# Processor.net
KiCad netlist of a schematic drawn in Altium Designer
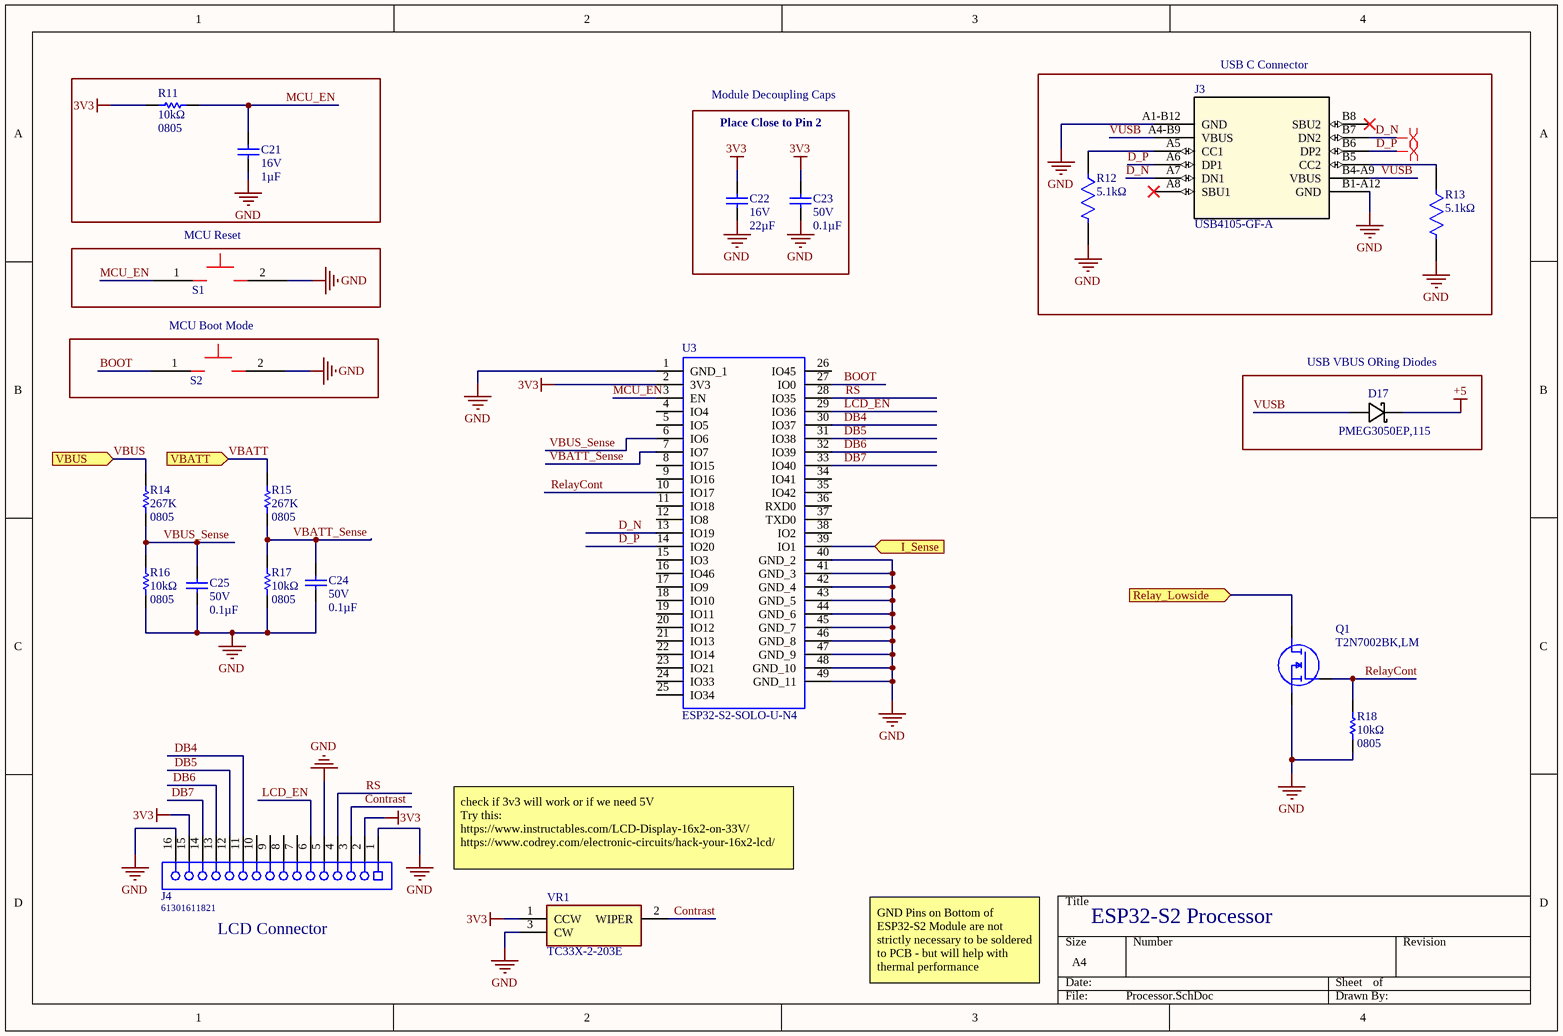
[diagram p0: Processor.SchDoc]

(export (version "E")
  (design (tool "Eeschema 10.0.6"))
  (components
    (comp (ref "C21")
      (value "GRM21BR71C105KA01L")
      (footprint "CAP0805")
      (description "CAP CER 1UF 16V X7R 0805")
      (fields
        (field (name "MANUFACTURER") "Murata Electronics North America")
        (field (name "TOLERANCE") "±10%")
        (field (name "VOLTAGE - RATED") "16V")
        (field (name "CAPACITANCE") "1µF")
      )
      (libsource (lib "Capacitors") (part "GRM21BR71C105KA01L"))
    )
    (comp (ref "C22")
      (value "CL21A226MOCLRNC")
      (footprint "CAP0805")
      (description "CAP CER 22UF 16V X5R 0805")
      (fields
        (field (name "TOLERANCE") "±20%")
        (field (name "VOLTAGE - RATED") "16V")
        (field (name "CAPACITANCE") "22µF")
      )
      (libsource (lib "Capacitors") (part "CL21A226MOCLRNC"))
    )
    (comp (ref "C23")
      (value "C0805C104K5RACTU")
      (footprint "CAP0805")
      (description "CAP CER 0.1UF 50V X7R 0805")
      (fields
        (field (name "TOLERANCE") "±10%")
        (field (name "VOLTAGE - RATED") "50V")
        (field (name "CAPACITANCE") "0.1µF")
      )
      (libsource (lib "Capacitors") (part "C0805C104K5RACTU"))
    )
    (comp (ref "C24")
      (value "C0805C104K5RACTU")
      (footprint "CAP0805")
      (description "CAP CER 0.1UF 50V X7R 0805")
      (fields
        (field (name "TOLERANCE") "±10%")
        (field (name "VOLTAGE - RATED") "50V")
        (field (name "CAPACITANCE") "0.1µF")
      )
      (libsource (lib "Capacitors") (part "C0805C104K5RACTU"))
    )
    (comp (ref "C25")
      (value "C0805C104K5RACTU")
      (footprint "CAP0805")
      (description "CAP CER 0.1UF 50V X7R 0805")
      (fields
        (field (name "TOLERANCE") "±10%")
        (field (name "VOLTAGE - RATED") "50V")
        (field (name "CAPACITANCE") "0.1µF")
      )
      (libsource (lib "Capacitors") (part "C0805C104K5RACTU"))
    )
    (comp (ref "D17")
      (value "D_PMEG3050EP,115")
      (footprint "SOD-128")
      (description "DIODE SCHOTTKY 360mV 30V 5A")
      (fields (field (name "MFG") "Nexperia") (field (name "MFG_PN") "PMEG3050EP,115"))
      (libsource (lib "Diodes") (part "D_PMEG3050EP,115"))
    )
    (comp (ref "J3")
      (value "USB4105-GF-A")
      (footprint "USB4105_GCT")
      (description "No Description Available")
      (fields (field (name "COPYRIGHT") "Copyright (C) 2022 Ultra Librarian. All rights reserved."))
      (libsource (lib "Connectors and Headers") (part "USB4105-GF-A"))
    )
    (comp (ref "J4")
      (value "61301611821")
      (footprint "61301611821")
      (description "THT Vertical Socket Header WR-PHD, Pitch 2.54 mm, Single Row, 16 pins")
      (fields (field (name "MANUFACTURER") "Wurth Elektronik") (field (name "PUBLISHER") "WurthElektronik"))
      (libsource (lib "Altium Content Vault") (part "WE-CN-1P-F-R16"))
    )
    (comp (ref "Q1")
      (value "T2N7002BK,LM")
      (footprint "SamacSys:TBAT54CLM")
      (description "MOSFET (N-Channel)")
      (fields (field (name "MOUSER PART NUMBER") "757-T2N7002BKLM"))
      (libsource (lib "*") (part "T2N7002BK,LM"))
    )
    (comp (ref "R11")
      (value "RC0805FR-0710KL")
      (footprint "RES0805")
      (description "RES SMD 10K OHM 1% 1/8W 0805")
      (fields
        (field (name "MANUFACTURER") "Yageo")
        (field (name "TOLERANCE") "±1%")
        (field (name "RESISTANCE") "10kΩ")
        (field (name "PACKAGE / CASE") "0805")
      )
      (libsource (lib "Resistors") (part "RC0805FR-0710KL"))
    )
    (comp (ref "R12")
      (value "CRCW08055K10FKEA")
      (footprint "FP-CRCW0805-e3-MFG")
      (description "RES Thick Film, 5.1kΩ, 1%, 0.125W, 100ppm/°C, 0805")
      (fields (field (name "TOLERANCE") "1%") (field (name "RESISTANCE") "5.1kΩ"))
      (libsource (lib "Altium Content Vault") (part "1029c3af85768c4190bb7ad29bc67b5"))
    )
    (comp (ref "R13")
      (value "CRCW08055K10FKEA")
      (footprint "FP-CRCW0805-e3-MFG")
      (description "RES Thick Film, 5.1kΩ, 1%, 0.125W, 100ppm/°C, 0805")
      (fields (field (name "TOLERANCE") "1%") (field (name "RESISTANCE") "5.1kΩ"))
      (libsource (lib "Altium Content Vault") (part "1029c3af85768c4190bb7ad29bc67b5"))
    )
    (comp (ref "R14")
      (value "RC0805FR-07267KL")
      (footprint "RESC2013X60X35NL10T20")
      (fields
        (field (name "MANUFACTURER") "Yageo")
        (field (name "RESISTANCE") "267K")
        (field (name "PACKAGE") "0805")
      )
      (libsource (lib "Altium Content Vault") (part "RES"))
    )
    (comp (ref "R15")
      (value "RC0805FR-07267KL")
      (footprint "RESC2013X60X35NL10T20")
      (fields
        (field (name "MANUFACTURER") "Yageo")
        (field (name "RESISTANCE") "267K")
        (field (name "PACKAGE") "0805")
      )
      (libsource (lib "Altium Content Vault") (part "RES"))
    )
    (comp (ref "R16")
      (value "RC0805FR-0710KL")
      (footprint "RES0805")
      (description "RES SMD 10K OHM 1% 1/8W 0805")
      (fields
        (field (name "MANUFACTURER") "Yageo")
        (field (name "TOLERANCE") "±1%")
        (field (name "RESISTANCE") "10kΩ")
        (field (name "PACKAGE / CASE") "0805")
      )
      (libsource (lib "Resistors") (part "RC0805FR-0710KL"))
    )
    (comp (ref "R17")
      (value "RC0805FR-0710KL")
      (footprint "RES0805")
      (description "RES SMD 10K OHM 1% 1/8W 0805")
      (fields
        (field (name "MANUFACTURER") "Yageo")
        (field (name "TOLERANCE") "±1%")
        (field (name "RESISTANCE") "10kΩ")
        (field (name "PACKAGE / CASE") "0805")
      )
      (libsource (lib "Resistors") (part "RC0805FR-0710KL"))
    )
    (comp (ref "R18")
      (value "RC0805FR-0710KL")
      (footprint "RES0805")
      (description "RES SMD 10K OHM 1% 1/8W 0805")
      (fields
        (field (name "MANUFACTURER") "Yageo")
        (field (name "TOLERANCE") "±1%")
        (field (name "RESISTANCE") "10kΩ")
        (field (name "PACKAGE / CASE") "0805")
      )
      (libsource (lib "Resistors") (part "RC0805FR-0710KL"))
    )
    (comp (ref "S1")
      (value "RESET")
      (footprint "Tactile_Button_3X6X2")
      (description "Tactile Button_3X6X2")
      (libsource (lib "Mechanical_Devices") (part "Tactile Button_3X6X2"))
    )
    (comp (ref "S2")
      (value "BOOT")
      (footprint "Tactile_Button_3X6X2")
      (description "Tactile Button_3X6X2")
      (libsource (lib "Mechanical_Devices") (part "Tactile Button_3X6X2"))
    )
    (comp (ref "U3")
      (value "ESP32-S2-SOLO-U-N4")
      (footprint "ESP32S2SOLOUN4")
      (description "WiFi Modules - 802.11 SMD module, ESP32-S2, 4 MB SPI flash, IPEX antenna")
      (fields (field (name "MOUSER PART NUMBER") "356-ESP32-S2-SOLOUN4"))
      (libsource (lib "Microcontrollers") (part "ESP32-S2-SOLO-U-N4"))
    )
    (comp (ref "VR1")
      (value "TC33X-2-203E")
      (footprint "SamacSys:TC33X2503E")
      (description "Variable Resistor")
      (fields (field (name "MOUSER PART NUMBER") "652-TC33X-2-203E"))
      (libsource (lib "*") (part "TC33X-2-203E"))
    )
  )
  (nets
    (net (code "1") (name "+5") (class "Default") (node (ref "D17") (pin "2") (pintype "passive")))
    (net (code "2") (name "/BOOT") (class "Default")
      (node (ref "S2") (pin "1") (pinfunction "1_1") (pintype "passive"))
      (node (ref "U3") (pin "27") (pinfunction "IO0_27") (pintype "passive"))
    )
    (net (code "3") (name "/Contrast") (class "Default")
      (node (ref "J4") (pin "3") (pinfunction "3_3") (pintype "passive"))
      (node (ref "VR1") (pin "2") (pinfunction "WIPER_2") (pintype "passive"))
    )
    (net (code "4") (name "/DB4") (class "Default")
      (node (ref "J4") (pin "11") (pinfunction "11_11") (pintype "passive"))
      (node (ref "U3") (pin "30") (pinfunction "IO37_30") (pintype "passive"))
    )
    (net (code "5") (name "/DB5") (class "Default")
      (node (ref "J4") (pin "12") (pinfunction "12_12") (pintype "passive"))
      (node (ref "U3") (pin "31") (pinfunction "IO38_31") (pintype "passive"))
    )
    (net (code "6") (name "/DB6") (class "Default")
      (node (ref "J4") (pin "13") (pinfunction "13_13") (pintype "passive"))
      (node (ref "U3") (pin "32") (pinfunction "IO39_32") (pintype "passive"))
    )
    (net (code "7") (name "/DB7") (class "Default")
      (node (ref "J4") (pin "14") (pinfunction "14_14") (pintype "passive"))
      (node (ref "U3") (pin "33") (pinfunction "IO40_33") (pintype "passive"))
    )
    (net (code "8") (name "/D_N") (class "Default")
      (node (ref "J3") (pin "A7") (pinfunction "DN1_A7") (pintype "bidirectional"))
      (node (ref "J3") (pin "B7") (pinfunction "DN2_B7") (pintype "bidirectional"))
      (node (ref "U3") (pin "13") (pinfunction "IO19_13") (pintype "passive"))
    )
    (net (code "9") (name "/D_P") (class "Default")
      (node (ref "J3") (pin "A6") (pinfunction "DP1_A6") (pintype "bidirectional"))
      (node (ref "J3") (pin "B6") (pinfunction "DP2_B6") (pintype "bidirectional"))
      (node (ref "U3") (pin "14") (pinfunction "IO20_14") (pintype "passive"))
    )
    (net (code "10") (name "/I_Sense") (class "Default")
      (node (ref "U3") (pin "39") (pinfunction "IO1_39") (pintype "passive"))
    )
    (net (code "11") (name "/LCD_EN") (class "Default")
      (node (ref "J4") (pin "6") (pinfunction "6_6") (pintype "passive"))
      (node (ref "U3") (pin "29") (pinfunction "IO36_29") (pintype "passive"))
    )
    (net (code "12") (name "/MCU_EN") (class "Default")
      (node (ref "C21") (pin "2") (pinfunction "2_2") (pintype "passive"))
      (node (ref "R11") (pin "1") (pinfunction "1_1") (pintype "passive"))
      (node (ref "S1") (pin "1") (pinfunction "1_1") (pintype "passive"))
      (node (ref "U3") (pin "3") (pinfunction "EN_3") (pintype "passive"))
    )
    (net (code "13") (name "/RS") (class "Default")
      (node (ref "J4") (pin "4") (pinfunction "4_4") (pintype "passive"))
      (node (ref "U3") (pin "28") (pinfunction "IO35_28") (pintype "passive"))
    )
    (net (code "14") (name "/RelayCont") (class "Default")
      (node (ref "Q1") (pin "1") (pinfunction "G_1") (pintype "passive"))
      (node (ref "R18") (pin "2") (pinfunction "2_2") (pintype "passive"))
      (node (ref "U3") (pin "10") (pinfunction "IO17_10") (pintype "passive"))
    )
    (net (code "15") (name "/Relay_Lowside") (class "Default")
      (node (ref "Q1") (pin "3") (pinfunction "D_3") (pintype "passive"))
    )
    (net (code "16") (name "/VBATT") (class "Default")
      (node (ref "R15") (pin "2") (pinfunction "2_2") (pintype "passive"))
    )
    (net (code "17") (name "/VBATT_Sense") (class "Default")
      (node (ref "C24") (pin "2") (pinfunction "2_2") (pintype "passive"))
      (node (ref "R15") (pin "1") (pinfunction "1_1") (pintype "passive"))
      (node (ref "R17") (pin "2") (pinfunction "2_2") (pintype "passive"))
      (node (ref "U3") (pin "7") (pinfunction "IO7_7") (pintype "passive"))
    )
    (net (code "18") (name "/VBUS") (class "Default")
      (node (ref "R14") (pin "2") (pinfunction "2_2") (pintype "passive"))
    )
    (net (code "19") (name "/VBUS_Sense") (class "Default")
      (node (ref "C25") (pin "2") (pinfunction "2_2") (pintype "passive"))
      (node (ref "R14") (pin "1") (pinfunction "1_1") (pintype "passive"))
      (node (ref "R16") (pin "1") (pinfunction "1_1") (pintype "passive"))
      (node (ref "U3") (pin "6") (pinfunction "IO6_6") (pintype "passive"))
    )
    (net (code "20") (name "/VUSB") (class "Default")
      (node (ref "D17") (pin "1") (pintype "passive"))
      (node (ref "J3") (pin "A4-B9") (pinfunction "VBUS_A4-B9") (pintype "power_in"))
      (node (ref "J3") (pin "B4-A9") (pinfunction "VBUS_B4-A9") (pintype "power_in"))
    )
    (net (code "21") (name "3V3") (class "Default")
      (node (ref "C22") (pin "2") (pinfunction "2_2") (pintype "passive"))
      (node (ref "C23") (pin "2") (pinfunction "2_2") (pintype "passive"))
      (node (ref "J4") (pin "15") (pinfunction "15_15") (pintype "passive"))
      (node (ref "J4") (pin "2") (pinfunction "2_2") (pintype "passive"))
      (node (ref "R11") (pin "2") (pinfunction "2_2") (pintype "passive"))
      (node (ref "U3") (pin "2") (pinfunction "3V3_2") (pintype "passive"))
      (node (ref "VR1") (pin "1") (pinfunction "CCW_1") (pintype "passive"))
    )
    (net (code "22") (name "GND") (class "Default")
      (node (ref "C21") (pin "1") (pinfunction "1_1") (pintype "passive"))
      (node (ref "C22") (pin "1") (pinfunction "1_1") (pintype "passive"))
      (node (ref "C23") (pin "1") (pinfunction "1_1") (pintype "passive"))
      (node (ref "C24") (pin "1") (pinfunction "1_1") (pintype "passive"))
      (node (ref "C25") (pin "1") (pinfunction "1_1") (pintype "passive"))
      (node (ref "J3") (pin "A1-B12") (pinfunction "GND_A1-B12") (pintype "passive"))
      (node (ref "J3") (pin "B1-A12") (pinfunction "GND_B1-A12") (pintype "passive"))
      (node (ref "J4") (pin "1") (pinfunction "1_1") (pintype "passive"))
      (node (ref "J4") (pin "16") (pinfunction "16_16") (pintype "passive"))
      (node (ref "J4") (pin "5") (pinfunction "5_5") (pintype "passive"))
      (node (ref "Q1") (pin "2") (pinfunction "S_2") (pintype "passive"))
      (node (ref "R12") (pin "2") (pinfunction "2_2") (pintype "passive"))
      (node (ref "R13") (pin "2") (pinfunction "2_2") (pintype "passive"))
      (node (ref "R16") (pin "2") (pinfunction "2_2") (pintype "passive"))
      (node (ref "R17") (pin "1") (pinfunction "1_1") (pintype "passive"))
      (node (ref "R18") (pin "1") (pinfunction "1_1") (pintype "passive"))
      (node (ref "S1") (pin "2") (pinfunction "2_2") (pintype "passive"))
      (node (ref "S2") (pin "2") (pinfunction "2_2") (pintype "passive"))
      (node (ref "U3") (pin "1") (pinfunction "GND_1_1") (pintype "passive"))
      (node (ref "U3") (pin "40") (pinfunction "GND_2_40") (pintype "passive"))
      (node (ref "U3") (pin "41") (pinfunction "GND_3_41") (pintype "passive"))
      (node (ref "U3") (pin "42") (pinfunction "GND_4_42") (pintype "passive"))
      (node (ref "U3") (pin "43") (pinfunction "GND_5_43") (pintype "passive"))
      (node (ref "U3") (pin "44") (pinfunction "GND_6_44") (pintype "passive"))
      (node (ref "U3") (pin "45") (pinfunction "GND_7_45") (pintype "passive"))
      (node (ref "U3") (pin "46") (pinfunction "GND_8_46") (pintype "passive"))
      (node (ref "U3") (pin "47") (pinfunction "GND_9_47") (pintype "passive"))
      (node (ref "U3") (pin "48") (pinfunction "GND_10_48") (pintype "passive"))
      (node (ref "U3") (pin "49") (pinfunction "GND_11_49") (pintype "passive"))
      (node (ref "VR1") (pin "3") (pinfunction "CW_3") (pintype "passive"))
    )
    (net (code "23") (name "Net-(J3-CC1)") (class "Default")
      (node (ref "J3") (pin "A5") (pinfunction "CC1_A5") (pintype "bidirectional"))
      (node (ref "R12") (pin "1") (pinfunction "1_1") (pintype "passive"))
    )
    (net (code "24") (name "Net-(J3-CC2)") (class "Default")
      (node (ref "J3") (pin "B5") (pinfunction "CC2_B5") (pintype "bidirectional"))
      (node (ref "R13") (pin "1") (pinfunction "1_1") (pintype "passive"))
    )
    (net (code "25") (name "unconnected-(J3-SBU1-PadA8)") (class "Default")
      (node (ref "J3") (pin "A8") (pinfunction "SBU1_A8") (pintype "bidirectional+no_connect"))
    )
    (net (code "26") (name "unconnected-(J3-SBU2-PadB8)") (class "Default")
      (node (ref "J3") (pin "B8") (pinfunction "SBU2_B8") (pintype "bidirectional+no_connect"))
    )
    (net (code "27") (name "unconnected-(J4-Pad7)") (class "Default")
      (node (ref "J4") (pin "7") (pinfunction "7_7") (pintype "passive"))
    )
    (net (code "28") (name "unconnected-(J4-Pad8)") (class "Default")
      (node (ref "J4") (pin "8") (pinfunction "8_8") (pintype "passive"))
    )
    (net (code "29") (name "unconnected-(J4-Pad9)") (class "Default")
      (node (ref "J4") (pin "9") (pinfunction "9_9") (pintype "passive"))
    )
    (net (code "30") (name "unconnected-(J4-Pad10)") (class "Default")
      (node (ref "J4") (pin "10") (pinfunction "10_10") (pintype "passive"))
    )
    (net (code "31") (name "unconnected-(U3-IO2-Pad38)") (class "Default")
      (node (ref "U3") (pin "38") (pinfunction "IO2_38") (pintype "passive"))
    )
    (net (code "32") (name "unconnected-(U3-IO3-Pad15)") (class "Default")
      (node (ref "U3") (pin "15") (pinfunction "IO3_15") (pintype "passive"))
    )
    (net (code "33") (name "unconnected-(U3-IO4-Pad4)") (class "Default")
      (node (ref "U3") (pin "4") (pinfunction "IO4_4") (pintype "passive"))
    )
    (net (code "34") (name "unconnected-(U3-IO5-Pad5)") (class "Default")
      (node (ref "U3") (pin "5") (pinfunction "IO5_5") (pintype "passive"))
    )
    (net (code "35") (name "unconnected-(U3-IO8-Pad12)") (class "Default")
      (node (ref "U3") (pin "12") (pinfunction "IO8_12") (pintype "passive"))
    )
    (net (code "36") (name "unconnected-(U3-IO9-Pad17)") (class "Default")
      (node (ref "U3") (pin "17") (pinfunction "IO9_17") (pintype "passive"))
    )
    (net (code "37") (name "unconnected-(U3-IO10-Pad18)") (class "Default")
      (node (ref "U3") (pin "18") (pinfunction "IO10_18") (pintype "passive"))
    )
    (net (code "38") (name "unconnected-(U3-IO11-Pad19)") (class "Default")
      (node (ref "U3") (pin "19") (pinfunction "IO11_19") (pintype "passive"))
    )
    (net (code "39") (name "unconnected-(U3-IO12-Pad20)") (class "Default")
      (node (ref "U3") (pin "20") (pinfunction "IO12_20") (pintype "passive"))
    )
    (net (code "40") (name "unconnected-(U3-IO13-Pad21)") (class "Default")
      (node (ref "U3") (pin "21") (pinfunction "IO13_21") (pintype "passive"))
    )
    (net (code "41") (name "unconnected-(U3-IO14-Pad22)") (class "Default")
      (node (ref "U3") (pin "22") (pinfunction "IO14_22") (pintype "passive"))
    )
    (net (code "42") (name "unconnected-(U3-IO15-Pad8)") (class "Default")
      (node (ref "U3") (pin "8") (pinfunction "IO15_8") (pintype "passive"))
    )
    (net (code "43") (name "unconnected-(U3-IO16-Pad9)") (class "Default")
      (node (ref "U3") (pin "9") (pinfunction "IO16_9") (pintype "passive"))
    )
    (net (code "44") (name "unconnected-(U3-IO18-Pad11)") (class "Default")
      (node (ref "U3") (pin "11") (pinfunction "IO18_11") (pintype "passive"))
    )
    (net (code "45") (name "unconnected-(U3-IO21-Pad23)") (class "Default")
      (node (ref "U3") (pin "23") (pinfunction "IO21_23") (pintype "passive"))
    )
    (net (code "46") (name "unconnected-(U3-IO33-Pad24)") (class "Default")
      (node (ref "U3") (pin "24") (pinfunction "IO33_24") (pintype "passive"))
    )
    (net (code "47") (name "unconnected-(U3-IO34-Pad25)") (class "Default")
      (node (ref "U3") (pin "25") (pinfunction "IO34_25") (pintype "passive"))
    )
    (net (code "48") (name "unconnected-(U3-IO41-Pad34)") (class "Default")
      (node (ref "U3") (pin "34") (pinfunction "IO41_34") (pintype "passive"))
    )
    (net (code "49") (name "unconnected-(U3-IO42-Pad35)") (class "Default")
      (node (ref "U3") (pin "35") (pinfunction "IO42_35") (pintype "passive"))
    )
    (net (code "50") (name "unconnected-(U3-IO45-Pad26)") (class "Default")
      (node (ref "U3") (pin "26") (pinfunction "IO45_26") (pintype "passive"))
    )
    (net (code "51") (name "unconnected-(U3-IO46-Pad16)") (class "Default")
      (node (ref "U3") (pin "16") (pinfunction "IO46_16") (pintype "passive"))
    )
    (net (code "52") (name "unconnected-(U3-RXD0-Pad36)") (class "Default")
      (node (ref "U3") (pin "36") (pinfunction "RXD0_36") (pintype "passive"))
    )
    (net (code "53") (name "unconnected-(U3-TXD0-Pad37)") (class "Default")
      (node (ref "U3") (pin "37") (pinfunction "TXD0_37") (pintype "passive"))
    )
  )
)
